# gardencore.net
KiCad netlist of a schematic drawn in EAGLE
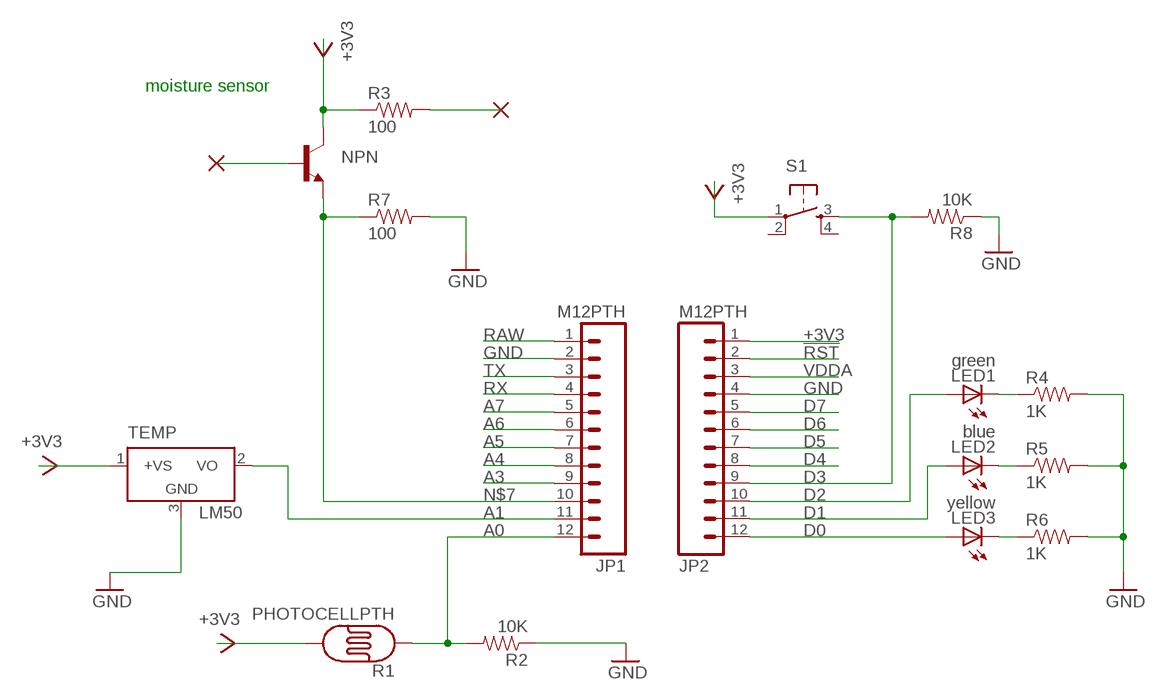
[diagram p0: schematic, sheet 1]

(export (version "E")
  (design (tool "Eeschema 10.0.6"))
  (components
    (comp (ref "JP1")
      (value "M12PTH")
      (footprint "eagle-import:1X12-SMALL-PADS")
      (libsource (lib "eagle-import") (part "M12PTH"))
    )
    (comp (ref "JP2")
      (value "M12PTH")
      (footprint "eagle-import:1X12-SMALL-PADS")
      (libsource (lib "eagle-import") (part "M12PTH"))
    )
    (comp (ref "LED1")
      (value "green")
      (footprint "eagle-import:LED3MM")
      (libsource (lib "eagle-import") (part "LED3MM"))
    )
    (comp (ref "LED2")
      (value "blue")
      (footprint "eagle-import:LED3MM")
      (libsource (lib "eagle-import") (part "LED3MM"))
    )
    (comp (ref "LED3")
      (value "yellow")
      (footprint "eagle-import:LED3MM")
      (libsource (lib "eagle-import") (part "LED3MM"))
    )
    (comp (ref "NPN")
      (value "TRANSISTOR_NPNTO92")
      (footprint "eagle-import:TO-92")
      (libsource (lib "eagle-import") (part "TRANSISTOR_NPNTO92"))
    )
    (comp (ref "R1")
      (value "PHOTOCELLPTH")
      (footprint "eagle-import:PHOTOCELL")
      (libsource (lib "eagle-import") (part "PHOTOCELLPTH"))
    )
    (comp (ref "R2")
      (value "10K")
      (footprint "eagle-import:AXIAL-0.3")
      (libsource (lib "eagle-import") (part "RESISTORAXIAL-0.3"))
    )
    (comp (ref "R3")
      (value "100")
      (footprint "eagle-import:AXIAL-0.3")
      (libsource (lib "eagle-import") (part "RESISTORAXIAL-0.3"))
    )
    (comp (ref "R4")
      (value "1K")
      (footprint "eagle-import:AXIAL-0.3")
      (libsource (lib "eagle-import") (part "RESISTORAXIAL-0.3"))
    )
    (comp (ref "R5")
      (value "1K")
      (footprint "eagle-import:AXIAL-0.3")
      (libsource (lib "eagle-import") (part "RESISTORAXIAL-0.3"))
    )
    (comp (ref "R6")
      (value "1K")
      (footprint "eagle-import:AXIAL-0.3")
      (libsource (lib "eagle-import") (part "RESISTORAXIAL-0.3"))
    )
    (comp (ref "R7")
      (value "100")
      (footprint "eagle-import:AXIAL-0.3")
      (libsource (lib "eagle-import") (part "RESISTORAXIAL-0.3"))
    )
    (comp (ref "R8")
      (value "10K")
      (footprint "eagle-import:AXIAL-0.3")
      (libsource (lib "eagle-import") (part "RESISTORAXIAL-0.3"))
    )
    (comp (ref "S1")
      (value "TAC_SWITCHPTH")
      (footprint "eagle-import:TACTILE-PTH")
      (libsource (lib "eagle-import") (part "TAC_SWITCHPTH"))
    )
    (comp (ref "TEMP")
      (value "LM50")
      (footprint "eagle-import:SOT23")
      (libsource (lib "eagle-import") (part "LM50"))
    )
  )
  (nets
    (net (code "1") (name "+3V3") (class "Default")
      (node (ref "JP2") (pin "1") (pinfunction "1_1") (pintype "passive"))
      (node (ref "NPN") (pin "3") (pinfunction "C_3") (pintype "passive"))
      (node (ref "R1") (pin "2") (pinfunction "P$2_2") (pintype "bidirectional"))
      (node (ref "R3") (pin "P$1") (pinfunction "1_P$1") (pintype "passive"))
      (node (ref "S1") (pin "1") (pinfunction "1_1") (pintype "passive"))
      (node (ref "TEMP") (pin "1") (pinfunction "+VS_1") (pintype "input"))
    )
    (net (code "2") (name "/A0") (class "Default")
      (node (ref "JP1") (pin "12") (pinfunction "12_12") (pintype "passive"))
      (node (ref "R1") (pin "1") (pinfunction "P$1_1") (pintype "bidirectional"))
      (node (ref "R2") (pin "P$2") (pinfunction "2_P$2") (pintype "passive"))
    )
    (net (code "3") (name "/A1") (class "Default")
      (node (ref "JP1") (pin "11") (pinfunction "11_11") (pintype "passive"))
      (node (ref "TEMP") (pin "2") (pinfunction "VO_2") (pintype "input"))
    )
    (net (code "4") (name "/A3") (class "Default")
      (node (ref "JP1") (pin "9") (pinfunction "9_9") (pintype "passive"))
    )
    (net (code "5") (name "/A4") (class "Default")
      (node (ref "JP1") (pin "8") (pinfunction "8_8") (pintype "passive"))
    )
    (net (code "6") (name "/A5") (class "Default")
      (node (ref "JP1") (pin "7") (pinfunction "7_7") (pintype "passive"))
    )
    (net (code "7") (name "/A6") (class "Default")
      (node (ref "JP1") (pin "6") (pinfunction "6_6") (pintype "passive"))
    )
    (net (code "8") (name "/A7") (class "Default")
      (node (ref "JP1") (pin "5") (pinfunction "5_5") (pintype "passive"))
    )
    (net (code "9") (name "/D0") (class "Default")
      (node (ref "JP2") (pin "12") (pinfunction "12_12") (pintype "passive"))
      (node (ref "LED3") (pin "A") (pinfunction "A_A") (pintype "passive"))
    )
    (net (code "10") (name "/D1") (class "Default")
      (node (ref "JP2") (pin "11") (pinfunction "11_11") (pintype "passive"))
      (node (ref "LED2") (pin "A") (pinfunction "A_A") (pintype "passive"))
    )
    (net (code "11") (name "/D2") (class "Default")
      (node (ref "JP2") (pin "10") (pinfunction "10_10") (pintype "passive"))
      (node (ref "LED1") (pin "A") (pinfunction "A_A") (pintype "passive"))
    )
    (net (code "12") (name "/D3") (class "Default")
      (node (ref "JP2") (pin "9") (pinfunction "9_9") (pintype "passive"))
      (node (ref "R8") (pin "P$2") (pinfunction "2_P$2") (pintype "passive"))
      (node (ref "S1") (pin "3") (pinfunction "3_3") (pintype "passive"))
    )
    (net (code "13") (name "/D4") (class "Default")
      (node (ref "JP2") (pin "8") (pinfunction "8_8") (pintype "passive"))
    )
    (net (code "14") (name "/D5") (class "Default")
      (node (ref "JP2") (pin "7") (pinfunction "7_7") (pintype "passive"))
    )
    (net (code "15") (name "/D6") (class "Default")
      (node (ref "JP2") (pin "6") (pinfunction "6_6") (pintype "passive"))
    )
    (net (code "16") (name "/D7") (class "Default")
      (node (ref "JP2") (pin "5") (pinfunction "5_5") (pintype "passive"))
    )
    (net (code "17") (name "/N$7") (class "Default")
      (node (ref "JP1") (pin "10") (pinfunction "10_10") (pintype "passive"))
      (node (ref "NPN") (pin "1") (pinfunction "E_1") (pintype "passive"))
      (node (ref "R7") (pin "P$1") (pinfunction "1_P$1") (pintype "passive"))
    )
    (net (code "18") (name "/RAW") (class "Default")
      (node (ref "JP1") (pin "1") (pinfunction "1_1") (pintype "passive"))
    )
    (net (code "19") (name "/RX") (class "Default")
      (node (ref "JP1") (pin "4") (pinfunction "4_4") (pintype "passive"))
    )
    (net (code "20") (name "/TX") (class "Default")
      (node (ref "JP1") (pin "3") (pinfunction "3_3") (pintype "passive"))
    )
    (net (code "21") (name "/VDDA") (class "Default")
      (node (ref "JP2") (pin "3") (pinfunction "3_3") (pintype "passive"))
    )
    (net (code "22") (name "/~{RST}") (class "Default")
      (node (ref "JP2") (pin "2") (pinfunction "2_2") (pintype "passive"))
    )
    (net (code "23") (name "GND") (class "Default")
      (node (ref "JP1") (pin "2") (pinfunction "2_2") (pintype "passive"))
      (node (ref "JP2") (pin "4") (pinfunction "4_4") (pintype "passive"))
      (node (ref "R2") (pin "P$1") (pinfunction "1_P$1") (pintype "passive"))
      (node (ref "R4") (pin "P$2") (pinfunction "2_P$2") (pintype "passive"))
      (node (ref "R5") (pin "P$2") (pinfunction "2_P$2") (pintype "passive"))
      (node (ref "R6") (pin "P$2") (pinfunction "2_P$2") (pintype "passive"))
      (node (ref "R7") (pin "P$2") (pinfunction "2_P$2") (pintype "passive"))
      (node (ref "R8") (pin "P$1") (pinfunction "1_P$1") (pintype "passive"))
      (node (ref "TEMP") (pin "3") (pinfunction "GND_3") (pintype "power_in"))
    )
    (net (code "24") (name "Net-(LED1-C)") (class "Default")
      (node (ref "LED1") (pin "K") (pinfunction "C_K") (pintype "passive"))
      (node (ref "R4") (pin "P$1") (pinfunction "1_P$1") (pintype "passive"))
    )
    (net (code "25") (name "Net-(LED2-C)") (class "Default")
      (node (ref "LED2") (pin "K") (pinfunction "C_K") (pintype "passive"))
      (node (ref "R5") (pin "P$1") (pinfunction "1_P$1") (pintype "passive"))
    )
    (net (code "26") (name "Net-(LED3-C)") (class "Default")
      (node (ref "LED3") (pin "K") (pinfunction "C_K") (pintype "passive"))
      (node (ref "R6") (pin "P$1") (pinfunction "1_P$1") (pintype "passive"))
    )
    (net (code "27") (name "unconnected-(NPN-B-Pad2)") (class "Default")
      (node (ref "NPN") (pin "2") (pinfunction "B_2") (pintype "passive"))
    )
    (net (code "28") (name "unconnected-(R3-2-PadP$2)") (class "Default")
      (node (ref "R3") (pin "P$2") (pinfunction "2_P$2") (pintype "passive"))
    )
    (net (code "29") (name "unconnected-(S1-Pad2)") (class "Default")
      (node (ref "S1") (pin "2") (pinfunction "2_2") (pintype "passive"))
    )
    (net (code "30") (name "unconnected-(S1-Pad4)") (class "Default")
      (node (ref "S1") (pin "4") (pinfunction "4_4") (pintype "passive"))
    )
  )
)
